# pcb_project.net
KiCad netlist of a schematic drawn in EAGLE
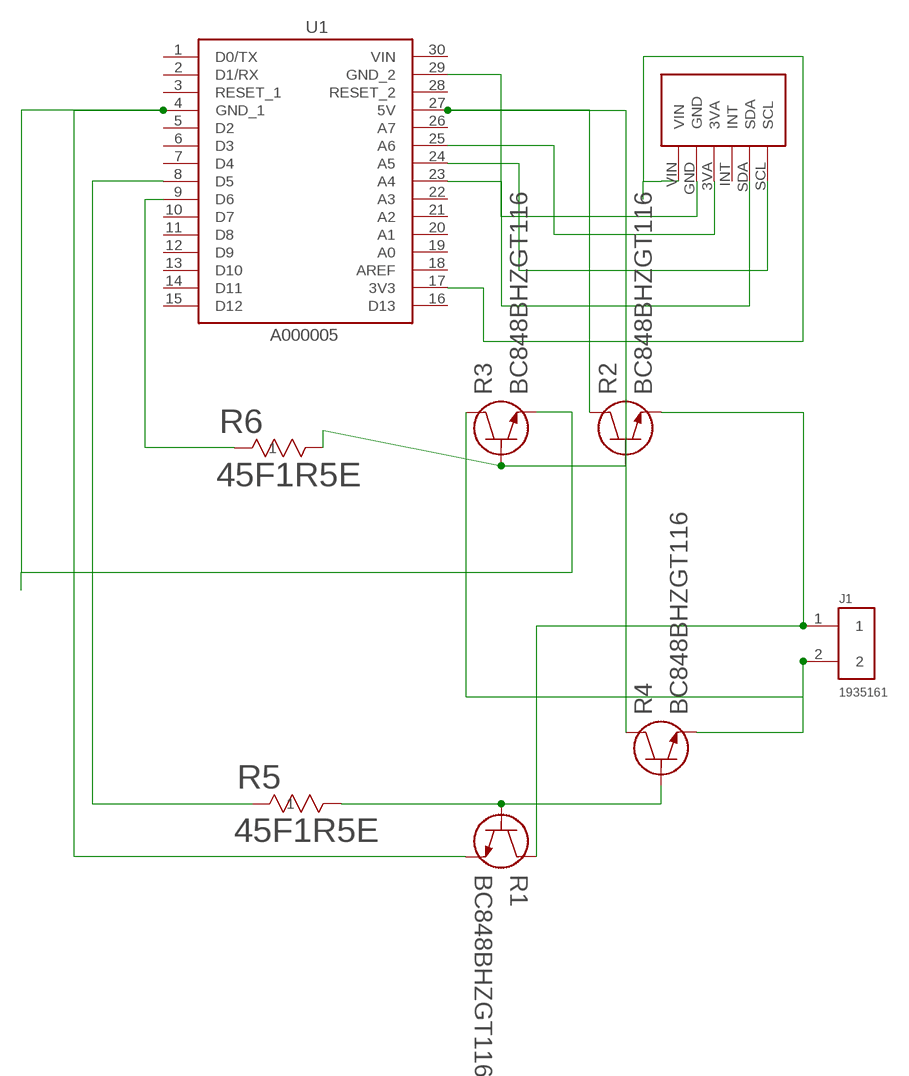
[diagram p0: schematic, sheet 1]

(export (version "E")
  (design (tool "Eeschema 10.0.6"))
  (components
    (comp (ref "J1")
      (value "1935161")
      (footprint "eagle-import:PHOENIX_1935161")
      (fields (field (name "DIGI-KEY_PART_NUMBER") "277-1667-ND") (field (name "MF") "Phoenix Contact"))
      (libsource (lib "eagle-import") (part "1935161"))
    )
    (comp (ref "R1")
      (value "BC848BHZGT116")
      (footprint "eagle-import:TRANS_BC847BHZGT116_ROM")
      (fields (field (name "COPYRIGHT") "Copyright (C) 2018 Accelerated Designs. All rights reserved"))
      (libsource (lib "eagle-import") (part "BC848BHZGT116"))
    )
    (comp (ref "R2")
      (value "BC848BHZGT116")
      (footprint "eagle-import:TRANS_BC847BHZGT116_ROM")
      (fields (field (name "COPYRIGHT") "Copyright (C) 2018 Accelerated Designs. All rights reserved"))
      (libsource (lib "eagle-import") (part "BC848BHZGT116"))
    )
    (comp (ref "R3")
      (value "BC848BHZGT116")
      (footprint "eagle-import:TRANS_BC847BHZGT116_ROM")
      (fields (field (name "COPYRIGHT") "Copyright (C) 2018 Accelerated Designs. All rights reserved"))
      (libsource (lib "eagle-import") (part "BC848BHZGT116"))
    )
    (comp (ref "R4")
      (value "BC848BHZGT116")
      (footprint "eagle-import:TRANS_BC847BHZGT116_ROM")
      (fields (field (name "COPYRIGHT") "Copyright (C) 2018 Accelerated Designs. All rights reserved"))
      (libsource (lib "eagle-import") (part "BC848BHZGT116"))
    )
    (comp (ref "R5")
      (value "45F1R5E")
      (footprint "eagle-import:RES_45_OHM")
      (libsource (lib "eagle-import") (part "45F1R5E"))
    )
    (comp (ref "R6")
      (value "45F1R5E")
      (footprint "eagle-import:RES_45_OHM")
      (libsource (lib "eagle-import") (part "45F1R5E"))
    )
    (comp (ref "U$1")
      (value "TSL2591")
      (footprint "eagle-import:TSL2591")
      (libsource (lib "eagle-import") (part "TSL2591"))
    )
    (comp (ref "U1")
      (value "A000005")
      (footprint "eagle-import:MODULE_A000005")
      (fields (field (name "DIGI-KEY_PART_NUMBER") "1050-1001-ND") (field (name "MF") "Arduino"))
      (libsource (lib "eagle-import") (part "A000005"))
    )
  )
  (nets
    (net (code "1") (name "/VIN") (class "Default")
      (node (ref "U1") (pin "30") (pinfunction "VIN_30") (pintype "power_in"))
    )
    (net (code "2") (name "Net-(R1-11)") (class "Default")
      (node (ref "R1") (pin "2") (pinfunction "11_2") (pintype "passive"))
      (node (ref "R4") (pin "2") (pinfunction "11_2") (pintype "passive"))
      (node (ref "R5") (pin "2") (pinfunction "2_2") (pintype "passive"))
    )
    (net (code "3") (name "Net-(R1-12)") (class "Default")
      (node (ref "J1") (pin "1") (pinfunction "1_1") (pintype "passive"))
      (node (ref "R1") (pin "1") (pinfunction "12_1") (pintype "passive"))
      (node (ref "R2") (pin "3") (pinfunction "13_3") (pintype "passive"))
    )
    (net (code "4") (name "Net-(R1-13)") (class "Default")
      (node (ref "R1") (pin "3") (pinfunction "13_3") (pintype "passive"))
      (node (ref "R3") (pin "3") (pinfunction "13_3") (pintype "passive"))
      (node (ref "U1") (pin "4") (pinfunction "GND_1_4") (pintype "power_in"))
    )
    (net (code "5") (name "Net-(R2-11)") (class "Default")
      (node (ref "R2") (pin "2") (pinfunction "11_2") (pintype "passive"))
      (node (ref "R3") (pin "2") (pinfunction "11_2") (pintype "passive"))
      (node (ref "R6") (pin "2") (pinfunction "2_2") (pintype "passive"))
    )
    (net (code "6") (name "Net-(R2-12)") (class "Default")
      (node (ref "R2") (pin "1") (pinfunction "12_1") (pintype "passive"))
      (node (ref "R4") (pin "1") (pinfunction "12_1") (pintype "passive"))
      (node (ref "U1") (pin "27") (pinfunction "5V_27") (pintype "power_in"))
    )
    (net (code "7") (name "Net-(R3-12)") (class "Default")
      (node (ref "J1") (pin "2") (pinfunction "2_2") (pintype "passive"))
      (node (ref "R3") (pin "1") (pinfunction "12_1") (pintype "passive"))
      (node (ref "R4") (pin "3") (pinfunction "13_3") (pintype "passive"))
    )
    (net (code "8") (name "Net-(U1-3V3)") (class "Default")
      (node (ref "U$1") (pin "VIN") (pinfunction "VIN_VIN") (pintype "bidirectional"))
      (node (ref "U1") (pin "17") (pinfunction "3V3_17") (pintype "power_in"))
    )
    (net (code "9") (name "Net-(U1-A4)") (class "Default")
      (node (ref "U$1") (pin "SDA") (pinfunction "SDA_SDA") (pintype "bidirectional"))
      (node (ref "U1") (pin "23") (pinfunction "A4_23") (pintype "input"))
    )
    (net (code "10") (name "Net-(U1-A5)") (class "Default")
      (node (ref "U$1") (pin "SCL") (pinfunction "SCL_SCL") (pintype "bidirectional"))
      (node (ref "U1") (pin "24") (pinfunction "A5_24") (pintype "input"))
    )
    (net (code "11") (name "Net-(U1-A6)") (class "Default")
      (node (ref "U$1") (pin "3VA") (pinfunction "3VA_3VA") (pintype "bidirectional"))
      (node (ref "U1") (pin "25") (pinfunction "A6_25") (pintype "input"))
    )
    (net (code "12") (name "Net-(U1-D5)") (class "Default")
      (node (ref "R5") (pin "1") (pinfunction "1_1") (pintype "passive"))
      (node (ref "U1") (pin "8") (pinfunction "D5_8") (pintype "bidirectional"))
    )
    (net (code "13") (name "Net-(U1-D6)") (class "Default")
      (node (ref "R6") (pin "1") (pinfunction "1_1") (pintype "passive"))
      (node (ref "U1") (pin "9") (pinfunction "D6_9") (pintype "bidirectional"))
    )
    (net (code "14") (name "Net-(U1-GND_2)") (class "Default")
      (node (ref "U$1") (pin "GND") (pinfunction "GND_GND") (pintype "bidirectional"))
      (node (ref "U1") (pin "29") (pinfunction "GND_2_29") (pintype "power_in"))
    )
    (net (code "15") (name "unconnected-(U$1-PadINT)") (class "Default")
      (node (ref "U$1") (pin "INT") (pinfunction "INT_INT") (pintype "bidirectional"))
    )
    (net (code "16") (name "unconnected-(U1-A0-Pad19)") (class "Default")
      (node (ref "U1") (pin "19") (pinfunction "A0_19") (pintype "input"))
    )
    (net (code "17") (name "unconnected-(U1-A1-Pad20)") (class "Default")
      (node (ref "U1") (pin "20") (pinfunction "A1_20") (pintype "input"))
    )
    (net (code "18") (name "unconnected-(U1-A2-Pad21)") (class "Default")
      (node (ref "U1") (pin "21") (pinfunction "A2_21") (pintype "input"))
    )
    (net (code "19") (name "unconnected-(U1-A3-Pad22)") (class "Default")
      (node (ref "U1") (pin "22") (pinfunction "A3_22") (pintype "input"))
    )
    (net (code "20") (name "unconnected-(U1-A7-Pad26)") (class "Default")
      (node (ref "U1") (pin "26") (pinfunction "A7_26") (pintype "input"))
    )
    (net (code "21") (name "unconnected-(U1-AREF-Pad18)") (class "Default")
      (node (ref "U1") (pin "18") (pinfunction "AREF_18") (pintype "input"))
    )
    (net (code "22") (name "unconnected-(U1-D0{slash}TX-Pad1)") (class "Default")
      (node (ref "U1") (pin "1") (pinfunction "D0/TX_1") (pintype "bidirectional"))
    )
    (net (code "23") (name "unconnected-(U1-D1{slash}RX-Pad2)") (class "Default")
      (node (ref "U1") (pin "2") (pinfunction "D1/RX_2") (pintype "bidirectional"))
    )
    (net (code "24") (name "unconnected-(U1-D2-Pad5)") (class "Default")
      (node (ref "U1") (pin "5") (pinfunction "D2_5") (pintype "bidirectional"))
    )
    (net (code "25") (name "unconnected-(U1-D3-Pad6)") (class "Default")
      (node (ref "U1") (pin "6") (pinfunction "D3_6") (pintype "bidirectional"))
    )
    (net (code "26") (name "unconnected-(U1-D4-Pad7)") (class "Default")
      (node (ref "U1") (pin "7") (pinfunction "D4_7") (pintype "bidirectional"))
    )
    (net (code "27") (name "unconnected-(U1-D7-Pad10)") (class "Default")
      (node (ref "U1") (pin "10") (pinfunction "D7_10") (pintype "bidirectional"))
    )
    (net (code "28") (name "unconnected-(U1-D8-Pad11)") (class "Default")
      (node (ref "U1") (pin "11") (pinfunction "D8_11") (pintype "bidirectional"))
    )
    (net (code "29") (name "unconnected-(U1-D9-Pad12)") (class "Default")
      (node (ref "U1") (pin "12") (pinfunction "D9_12") (pintype "bidirectional"))
    )
    (net (code "30") (name "unconnected-(U1-D10-Pad13)") (class "Default")
      (node (ref "U1") (pin "13") (pinfunction "D10_13") (pintype "bidirectional"))
    )
    (net (code "31") (name "unconnected-(U1-D11-Pad14)") (class "Default")
      (node (ref "U1") (pin "14") (pinfunction "D11_14") (pintype "bidirectional"))
    )
    (net (code "32") (name "unconnected-(U1-D12-Pad15)") (class "Default")
      (node (ref "U1") (pin "15") (pinfunction "D12_15") (pintype "bidirectional"))
    )
    (net (code "33") (name "unconnected-(U1-D13-Pad16)") (class "Default")
      (node (ref "U1") (pin "16") (pinfunction "D13_16") (pintype "bidirectional"))
    )
    (net (code "34") (name "unconnected-(U1-RESET_1-Pad3)") (class "Default")
      (node (ref "U1") (pin "3") (pinfunction "RESET_1_3") (pintype "input"))
    )
    (net (code "35") (name "unconnected-(U1-RESET_2-Pad28)") (class "Default")
      (node (ref "U1") (pin "28") (pinfunction "RESET_2_28") (pintype "input"))
    )
  )
)
